# ValveModule_r2.net
KiCad netlist of a schematic drawn in EAGLE
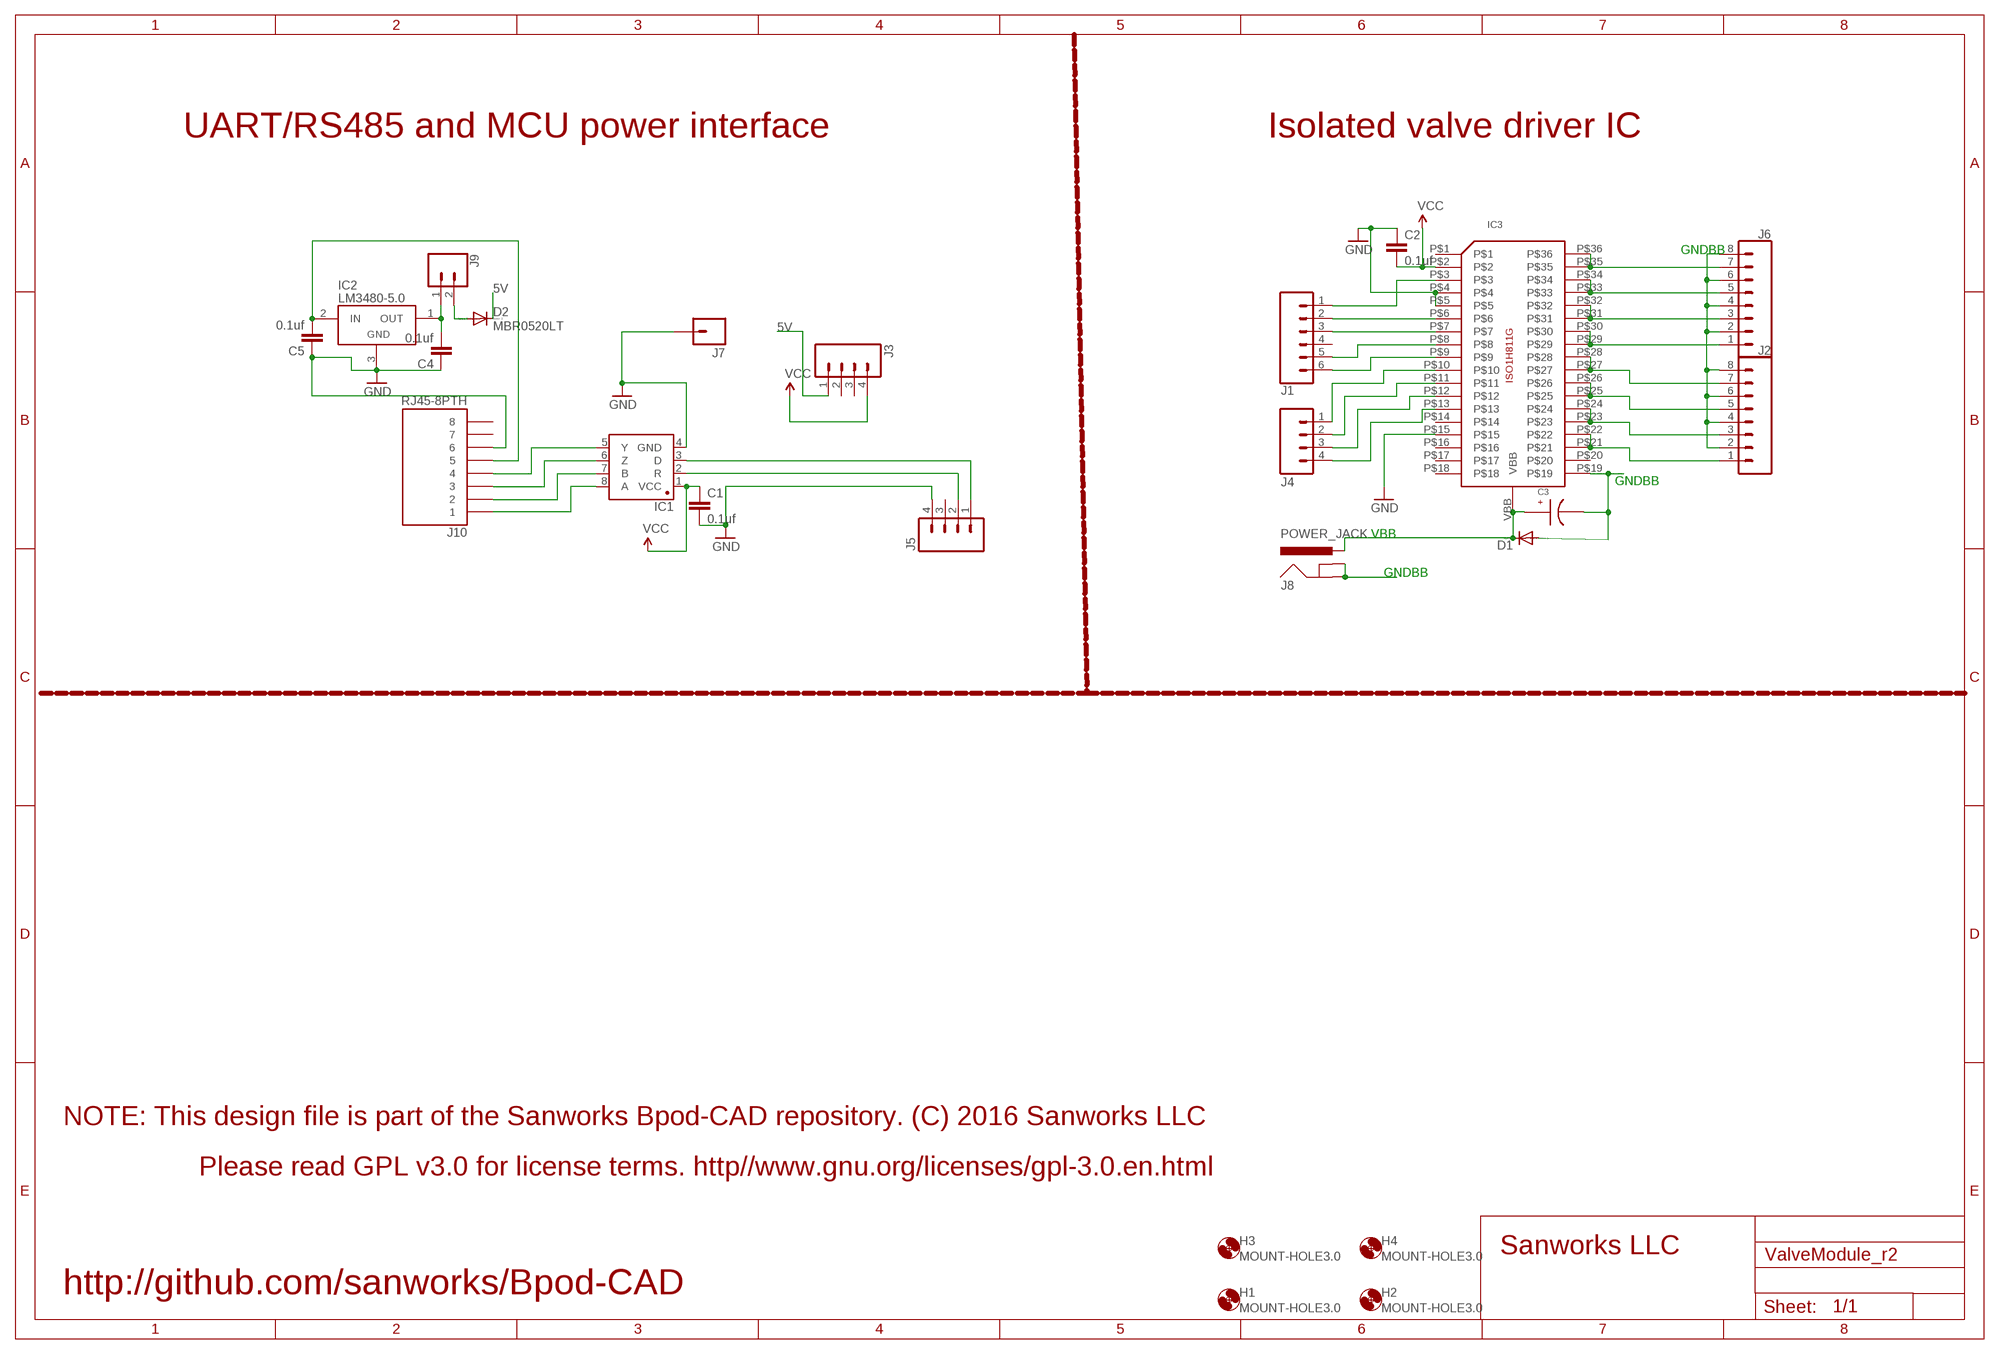
[diagram p0: schematic, sheet 1]

(export (version "E")
  (design (tool "Eeschema 10.0.6"))
  (components
    (comp (ref "C1")
      (value "0.1uf")
      (footprint "eagle-import:1206")
      (libsource (lib "eagle-import") (part "CAP1206"))
    )
    (comp (ref "C2")
      (value "0.1uf")
      (footprint "eagle-import:1206")
      (libsource (lib "eagle-import") (part "CAP1206"))
    )
    (comp (ref "C3")
      (value "EEE-FK1H100UR")
      (footprint "eagle-import:EEE-FK1H100UR")
      (libsource (lib "eagle-import") (part "EEE-FK1H100UR"))
    )
    (comp (ref "C4")
      (value "0.1uf")
      (footprint "eagle-import:1206")
      (libsource (lib "eagle-import") (part "CAP1206"))
    )
    (comp (ref "C5")
      (value "0.1uf")
      (footprint "eagle-import:1206")
      (libsource (lib "eagle-import") (part "CAP1206"))
    )
    (comp (ref "D1")
      (value "DIODE-DO214AA")
      (footprint "eagle-import:DO214AA")
      (libsource (lib "eagle-import") (part "DIODE-DO214AA"))
    )
    (comp (ref "D2")
      (value "MBR0520LT")
      (footprint "eagle-import:SOD123")
      (libsource (lib "eagle-import") (part "MBR0520LT"))
    )
    (comp (ref "H1")
      (value "MOUNT-HOLE3.0")
      (footprint "eagle-import:3,0")
      (libsource (lib "eagle-import") (part "MOUNT-HOLE3.0"))
    )
    (comp (ref "H2")
      (value "MOUNT-HOLE3.0")
      (footprint "eagle-import:3,0")
      (libsource (lib "eagle-import") (part "MOUNT-HOLE3.0"))
    )
    (comp (ref "H3")
      (value "MOUNT-HOLE3.0")
      (footprint "eagle-import:3,0")
      (libsource (lib "eagle-import") (part "MOUNT-HOLE3.0"))
    )
    (comp (ref "H4")
      (value "MOUNT-HOLE3.0")
      (footprint "eagle-import:3,0")
      (libsource (lib "eagle-import") (part "MOUNT-HOLE3.0"))
    )
    (comp (ref "IC1")
      (value "SN65HVD31DR")
      (footprint "eagle-import:SO08")
      (libsource (lib "eagle-import") (part "SN65HVD31DR"))
    )
    (comp (ref "IC2")
      (value "LM3480-5.0")
      (footprint "eagle-import:SOT-23-3")
      (libsource (lib "eagle-import") (part "LM3480-5.0"))
    )
    (comp (ref "IC3")
      (value "ISO1H811G")
      (footprint "eagle-import:ISO1H811G")
      (libsource (lib "eagle-import") (part "ISO1H811G"))
    )
    (comp (ref "J1")
      (value "CONN_06SILK_FEMALE_PTH")
      (footprint "eagle-import:1X06")
      (libsource (lib "eagle-import") (part "CONN_06SILK_FEMALE_PTH"))
    )
    (comp (ref "J2")
      (value "CONN_083.5MM-8")
      (footprint "eagle-import:SCREWTERMINAL-3.5MM-8")
      (libsource (lib "eagle-import") (part "CONN_083.5MM-8"))
    )
    (comp (ref "J3")
      (value "M04PTH")
      (footprint "eagle-import:1X04")
      (libsource (lib "eagle-import") (part "M04PTH"))
    )
    (comp (ref "J4")
      (value "M04PTH")
      (footprint "eagle-import:1X04")
      (libsource (lib "eagle-import") (part "M04PTH"))
    )
    (comp (ref "J5")
      (value "M04PTH")
      (footprint "eagle-import:1X04")
      (libsource (lib "eagle-import") (part "M04PTH"))
    )
    (comp (ref "J6")
      (value "CONN_083.5MM-8")
      (footprint "eagle-import:SCREWTERMINAL-3.5MM-8")
      (libsource (lib "eagle-import") (part "CONN_083.5MM-8"))
    )
    (comp (ref "J7")
      (value "M01PTH")
      (footprint "eagle-import:1X01")
      (libsource (lib "eagle-import") (part "M01PTH"))
    )
    (comp (ref "J8")
      (value "POWER_JACK")
      (footprint "eagle-import:POWER_JACK_PTH")
      (libsource (lib "eagle-import") (part "POWER_JACK"))
    )
    (comp (ref "J9")
      (value "CONN_02")
      (footprint "eagle-import:1X02")
      (libsource (lib "eagle-import") (part "CONN_02"))
    )
    (comp (ref "J10")
      (value "RJ45-8PTH")
      (footprint "eagle-import:RJ45-8")
      (libsource (lib "eagle-import") (part "RJ45-8PTH"))
    )
  )
  (nets
    (net (code "1") (name "/5V") (class "Default")
      (node (ref "D2") (pin "C") (pinfunction "C_C") (pintype "passive"))
      (node (ref "J3") (pin "1") (pinfunction "1_1") (pintype "passive"))
    )
    (net (code "2") (name "/GNDBB") (class "Default")
      (node (ref "C3") (pin "CATHODE") (pinfunction "CATHODE_CATHODE") (pintype "bidirectional"))
      (node (ref "D1") (pin "A") (pinfunction "A_A") (pintype "passive"))
      (node (ref "IC3") (pin "P$19") (pinfunction "P$19_P$19") (pintype "bidirectional"))
      (node (ref "J2") (pin "2") (pinfunction "2_2") (pintype "passive"))
      (node (ref "J2") (pin "4") (pinfunction "4_4") (pintype "passive"))
      (node (ref "J2") (pin "6") (pinfunction "6_6") (pintype "passive"))
      (node (ref "J2") (pin "8") (pinfunction "8_8") (pintype "passive"))
      (node (ref "J6") (pin "2") (pinfunction "2_2") (pintype "passive"))
      (node (ref "J6") (pin "4") (pinfunction "4_4") (pintype "passive"))
      (node (ref "J6") (pin "6") (pinfunction "6_6") (pintype "passive"))
      (node (ref "J6") (pin "8") (pinfunction "8_8") (pintype "passive"))
      (node (ref "J8") (pin "GND") (pinfunction "GND_GND") (pintype "bidirectional"))
      (node (ref "J8") (pin "GNDBREAK") (pinfunction "GNDBREAK_GNDBREAK") (pintype "bidirectional"))
    )
    (net (code "3") (name "GND") (class "Default")
      (node (ref "C1") (pin "2") (pinfunction "2_2") (pintype "passive"))
      (node (ref "C2") (pin "1") (pinfunction "1_1") (pintype "passive"))
      (node (ref "C4") (pin "1") (pinfunction "1_1") (pintype "passive"))
      (node (ref "C5") (pin "1") (pinfunction "1_1") (pintype "passive"))
      (node (ref "IC1") (pin "4") (pinfunction "GND_4") (pintype "bidirectional"))
      (node (ref "IC2") (pin "3") (pinfunction "GND_3") (pintype "power_in"))
      (node (ref "IC3") (pin "P$15") (pinfunction "P$15_P$15") (pintype "bidirectional"))
      (node (ref "IC3") (pin "P$4") (pinfunction "P$4_P$4") (pintype "bidirectional"))
      (node (ref "IC3") (pin "P$5") (pinfunction "P$5_P$5") (pintype "bidirectional"))
      (node (ref "J10") (pin "6") (pinfunction "6_6") (pintype "bidirectional"))
      (node (ref "J5") (pin "4") (pinfunction "4_4") (pintype "passive"))
      (node (ref "J7") (pin "1") (pinfunction "1_1") (pintype "passive"))
    )
    (net (code "4") (name "Net-(C3-PadANODE)") (class "Default")
      (node (ref "C3") (pin "ANODE") (pinfunction "ANODE_ANODE") (pintype "bidirectional"))
      (node (ref "D1") (pin "C") (pinfunction "C_C") (pintype "passive"))
      (node (ref "IC3") (pin "VBB") (pinfunction "VBB_VBB") (pintype "bidirectional"))
      (node (ref "J8") (pin "PWR") (pinfunction "PWR_PWR") (pintype "bidirectional"))
    )
    (net (code "5") (name "Net-(D2-PadA)") (class "Default")
      (node (ref "D2") (pin "A") (pinfunction "A_A") (pintype "passive"))
      (node (ref "J9") (pin "2") (pinfunction "2_2") (pintype "passive"))
    )
    (net (code "6") (name "Net-(IC1-A)") (class "Default")
      (node (ref "IC1") (pin "8") (pinfunction "A_8") (pintype "bidirectional"))
      (node (ref "J10") (pin "1") (pinfunction "1_1") (pintype "bidirectional"))
    )
    (net (code "7") (name "Net-(IC1-B)") (class "Default")
      (node (ref "IC1") (pin "7") (pinfunction "B_7") (pintype "bidirectional"))
      (node (ref "J10") (pin "2") (pinfunction "2_2") (pintype "bidirectional"))
    )
    (net (code "8") (name "Net-(IC1-D)") (class "Default")
      (node (ref "IC1") (pin "3") (pinfunction "D_3") (pintype "bidirectional"))
      (node (ref "J5") (pin "1") (pinfunction "1_1") (pintype "passive"))
    )
    (net (code "9") (name "Net-(IC1-R)") (class "Default")
      (node (ref "IC1") (pin "2") (pinfunction "R_2") (pintype "bidirectional"))
      (node (ref "J5") (pin "2") (pinfunction "2_2") (pintype "passive"))
    )
    (net (code "10") (name "Net-(IC1-Y)") (class "Default")
      (node (ref "IC1") (pin "5") (pinfunction "Y_5") (pintype "bidirectional"))
      (node (ref "J10") (pin "4") (pinfunction "4_4") (pintype "bidirectional"))
    )
    (net (code "11") (name "Net-(IC1-Z)") (class "Default")
      (node (ref "IC1") (pin "6") (pinfunction "Z_6") (pintype "bidirectional"))
      (node (ref "J10") (pin "3") (pinfunction "3_3") (pintype "bidirectional"))
    )
    (net (code "12") (name "Net-(IC2-IN)") (class "Default")
      (node (ref "C5") (pin "2") (pinfunction "2_2") (pintype "passive"))
      (node (ref "IC2") (pin "2") (pinfunction "IN_2") (pintype "power_in"))
      (node (ref "J10") (pin "5") (pinfunction "5_5") (pintype "bidirectional"))
    )
    (net (code "13") (name "Net-(IC2-OUT)") (class "Default")
      (node (ref "C4") (pin "2") (pinfunction "2_2") (pintype "passive"))
      (node (ref "IC2") (pin "1") (pinfunction "OUT_1") (pintype "power_in"))
      (node (ref "J9") (pin "1") (pinfunction "1_1") (pintype "passive"))
    )
    (net (code "14") (name "Net-(IC3-PadP$3)") (class "Default")
      (node (ref "IC3") (pin "P$3") (pinfunction "P$3_P$3") (pintype "bidirectional"))
      (node (ref "J1") (pin "1") (pinfunction "1_1") (pintype "passive"))
    )
    (net (code "15") (name "Net-(IC3-PadP$6)") (class "Default")
      (node (ref "IC3") (pin "P$6") (pinfunction "P$6_P$6") (pintype "bidirectional"))
      (node (ref "J1") (pin "2") (pinfunction "2_2") (pintype "passive"))
    )
    (net (code "16") (name "Net-(IC3-PadP$7)") (class "Default")
      (node (ref "IC3") (pin "P$7") (pinfunction "P$7_P$7") (pintype "bidirectional"))
      (node (ref "J1") (pin "3") (pinfunction "3_3") (pintype "passive"))
    )
    (net (code "17") (name "Net-(IC3-PadP$8)") (class "Default")
      (node (ref "IC3") (pin "P$8") (pinfunction "P$8_P$8") (pintype "bidirectional"))
      (node (ref "J1") (pin "5") (pinfunction "5_5") (pintype "passive"))
    )
    (net (code "18") (name "Net-(IC3-PadP$9)") (class "Default")
      (node (ref "IC3") (pin "P$9") (pinfunction "P$9_P$9") (pintype "bidirectional"))
      (node (ref "J1") (pin "6") (pinfunction "6_6") (pintype "passive"))
    )
    (net (code "19") (name "Net-(IC3-PadP$10)") (class "Default")
      (node (ref "IC3") (pin "P$10") (pinfunction "P$10_P$10") (pintype "bidirectional"))
      (node (ref "J4") (pin "1") (pinfunction "1_1") (pintype "passive"))
    )
    (net (code "20") (name "Net-(IC3-PadP$11)") (class "Default")
      (node (ref "IC3") (pin "P$11") (pinfunction "P$11_P$11") (pintype "bidirectional"))
      (node (ref "J4") (pin "2") (pinfunction "2_2") (pintype "passive"))
    )
    (net (code "21") (name "Net-(IC3-PadP$12)") (class "Default")
      (node (ref "IC3") (pin "P$12") (pinfunction "P$12_P$12") (pintype "bidirectional"))
      (node (ref "J4") (pin "3") (pinfunction "3_3") (pintype "passive"))
    )
    (net (code "22") (name "Net-(IC3-PadP$13)") (class "Default")
      (node (ref "IC3") (pin "P$13") (pinfunction "P$13_P$13") (pintype "bidirectional"))
      (node (ref "J4") (pin "4") (pinfunction "4_4") (pintype "passive"))
    )
    (net (code "23") (name "Net-(IC3-PadP$21)") (class "Default")
      (node (ref "IC3") (pin "P$21") (pinfunction "P$21_P$21") (pintype "bidirectional"))
      (node (ref "IC3") (pin "P$22") (pinfunction "P$22_P$22") (pintype "bidirectional"))
      (node (ref "J2") (pin "1") (pinfunction "1_1") (pintype "passive"))
    )
    (net (code "24") (name "Net-(IC3-PadP$23)") (class "Default")
      (node (ref "IC3") (pin "P$23") (pinfunction "P$23_P$23") (pintype "bidirectional"))
      (node (ref "IC3") (pin "P$24") (pinfunction "P$24_P$24") (pintype "bidirectional"))
      (node (ref "J2") (pin "3") (pinfunction "3_3") (pintype "passive"))
    )
    (net (code "25") (name "Net-(IC3-PadP$25)") (class "Default")
      (node (ref "IC3") (pin "P$25") (pinfunction "P$25_P$25") (pintype "bidirectional"))
      (node (ref "IC3") (pin "P$26") (pinfunction "P$26_P$26") (pintype "bidirectional"))
      (node (ref "J2") (pin "5") (pinfunction "5_5") (pintype "passive"))
    )
    (net (code "26") (name "Net-(IC3-PadP$27)") (class "Default")
      (node (ref "IC3") (pin "P$27") (pinfunction "P$27_P$27") (pintype "bidirectional"))
      (node (ref "IC3") (pin "P$28") (pinfunction "P$28_P$28") (pintype "bidirectional"))
      (node (ref "J2") (pin "7") (pinfunction "7_7") (pintype "passive"))
    )
    (net (code "27") (name "Net-(IC3-PadP$29)") (class "Default")
      (node (ref "IC3") (pin "P$29") (pinfunction "P$29_P$29") (pintype "bidirectional"))
      (node (ref "IC3") (pin "P$30") (pinfunction "P$30_P$30") (pintype "bidirectional"))
      (node (ref "J6") (pin "1") (pinfunction "1_1") (pintype "passive"))
    )
    (net (code "28") (name "Net-(IC3-PadP$31)") (class "Default")
      (node (ref "IC3") (pin "P$31") (pinfunction "P$31_P$31") (pintype "bidirectional"))
      (node (ref "IC3") (pin "P$32") (pinfunction "P$32_P$32") (pintype "bidirectional"))
      (node (ref "J6") (pin "3") (pinfunction "3_3") (pintype "passive"))
    )
    (net (code "29") (name "Net-(IC3-PadP$33)") (class "Default")
      (node (ref "IC3") (pin "P$33") (pinfunction "P$33_P$33") (pintype "bidirectional"))
      (node (ref "IC3") (pin "P$34") (pinfunction "P$34_P$34") (pintype "bidirectional"))
      (node (ref "J6") (pin "5") (pinfunction "5_5") (pintype "passive"))
    )
    (net (code "30") (name "Net-(IC3-PadP$35)") (class "Default")
      (node (ref "IC3") (pin "P$35") (pinfunction "P$35_P$35") (pintype "bidirectional"))
      (node (ref "IC3") (pin "P$36") (pinfunction "P$36_P$36") (pintype "bidirectional"))
      (node (ref "J6") (pin "7") (pinfunction "7_7") (pintype "passive"))
    )
    (net (code "31") (name "VCC") (class "Default")
      (node (ref "C1") (pin "1") (pinfunction "1_1") (pintype "passive"))
      (node (ref "C2") (pin "2") (pinfunction "2_2") (pintype "passive"))
      (node (ref "IC1") (pin "1") (pinfunction "VCC_1") (pintype "bidirectional"))
      (node (ref "IC3") (pin "P$2") (pinfunction "P$2_P$2") (pintype "bidirectional"))
      (node (ref "J3") (pin "4") (pinfunction "4_4") (pintype "passive"))
    )
    (net (code "32") (name "unconnected-(IC3-PadP$1)") (class "Default")
      (node (ref "IC3") (pin "P$1") (pinfunction "P$1_P$1") (pintype "bidirectional"))
    )
    (net (code "33") (name "unconnected-(IC3-PadP$14)") (class "Default")
      (node (ref "IC3") (pin "P$14") (pinfunction "P$14_P$14") (pintype "bidirectional"))
    )
    (net (code "34") (name "unconnected-(IC3-PadP$16)") (class "Default")
      (node (ref "IC3") (pin "P$16") (pinfunction "P$16_P$16") (pintype "bidirectional"))
    )
    (net (code "35") (name "unconnected-(IC3-PadP$17)") (class "Default")
      (node (ref "IC3") (pin "P$17") (pinfunction "P$17_P$17") (pintype "bidirectional"))
    )
    (net (code "36") (name "unconnected-(IC3-PadP$18)") (class "Default")
      (node (ref "IC3") (pin "P$18") (pinfunction "P$18_P$18") (pintype "bidirectional"))
    )
    (net (code "37") (name "unconnected-(IC3-PadP$20)") (class "Default")
      (node (ref "IC3") (pin "P$20") (pinfunction "P$20_P$20") (pintype "bidirectional"))
    )
    (net (code "38") (name "unconnected-(J1-Pad4)") (class "Default")
      (node (ref "J1") (pin "4") (pinfunction "4_4") (pintype "passive"))
    )
    (net (code "39") (name "unconnected-(J3-Pad2)") (class "Default")
      (node (ref "J3") (pin "2") (pinfunction "2_2") (pintype "passive"))
    )
    (net (code "40") (name "unconnected-(J3-Pad3)") (class "Default")
      (node (ref "J3") (pin "3") (pinfunction "3_3") (pintype "passive"))
    )
    (net (code "41") (name "unconnected-(J5-Pad3)") (class "Default")
      (node (ref "J5") (pin "3") (pinfunction "3_3") (pintype "passive"))
    )
    (net (code "42") (name "unconnected-(J10-Pad7)") (class "Default")
      (node (ref "J10") (pin "7") (pinfunction "7_7") (pintype "bidirectional"))
    )
    (net (code "43") (name "unconnected-(J10-Pad8)") (class "Default")
      (node (ref "J10") (pin "8") (pinfunction "8_8") (pintype "bidirectional"))
    )
  )
)
